# BG0249_R1M1E1_BW235_IMX378.net
KiCad netlist of a schematic drawn in Altium Designer
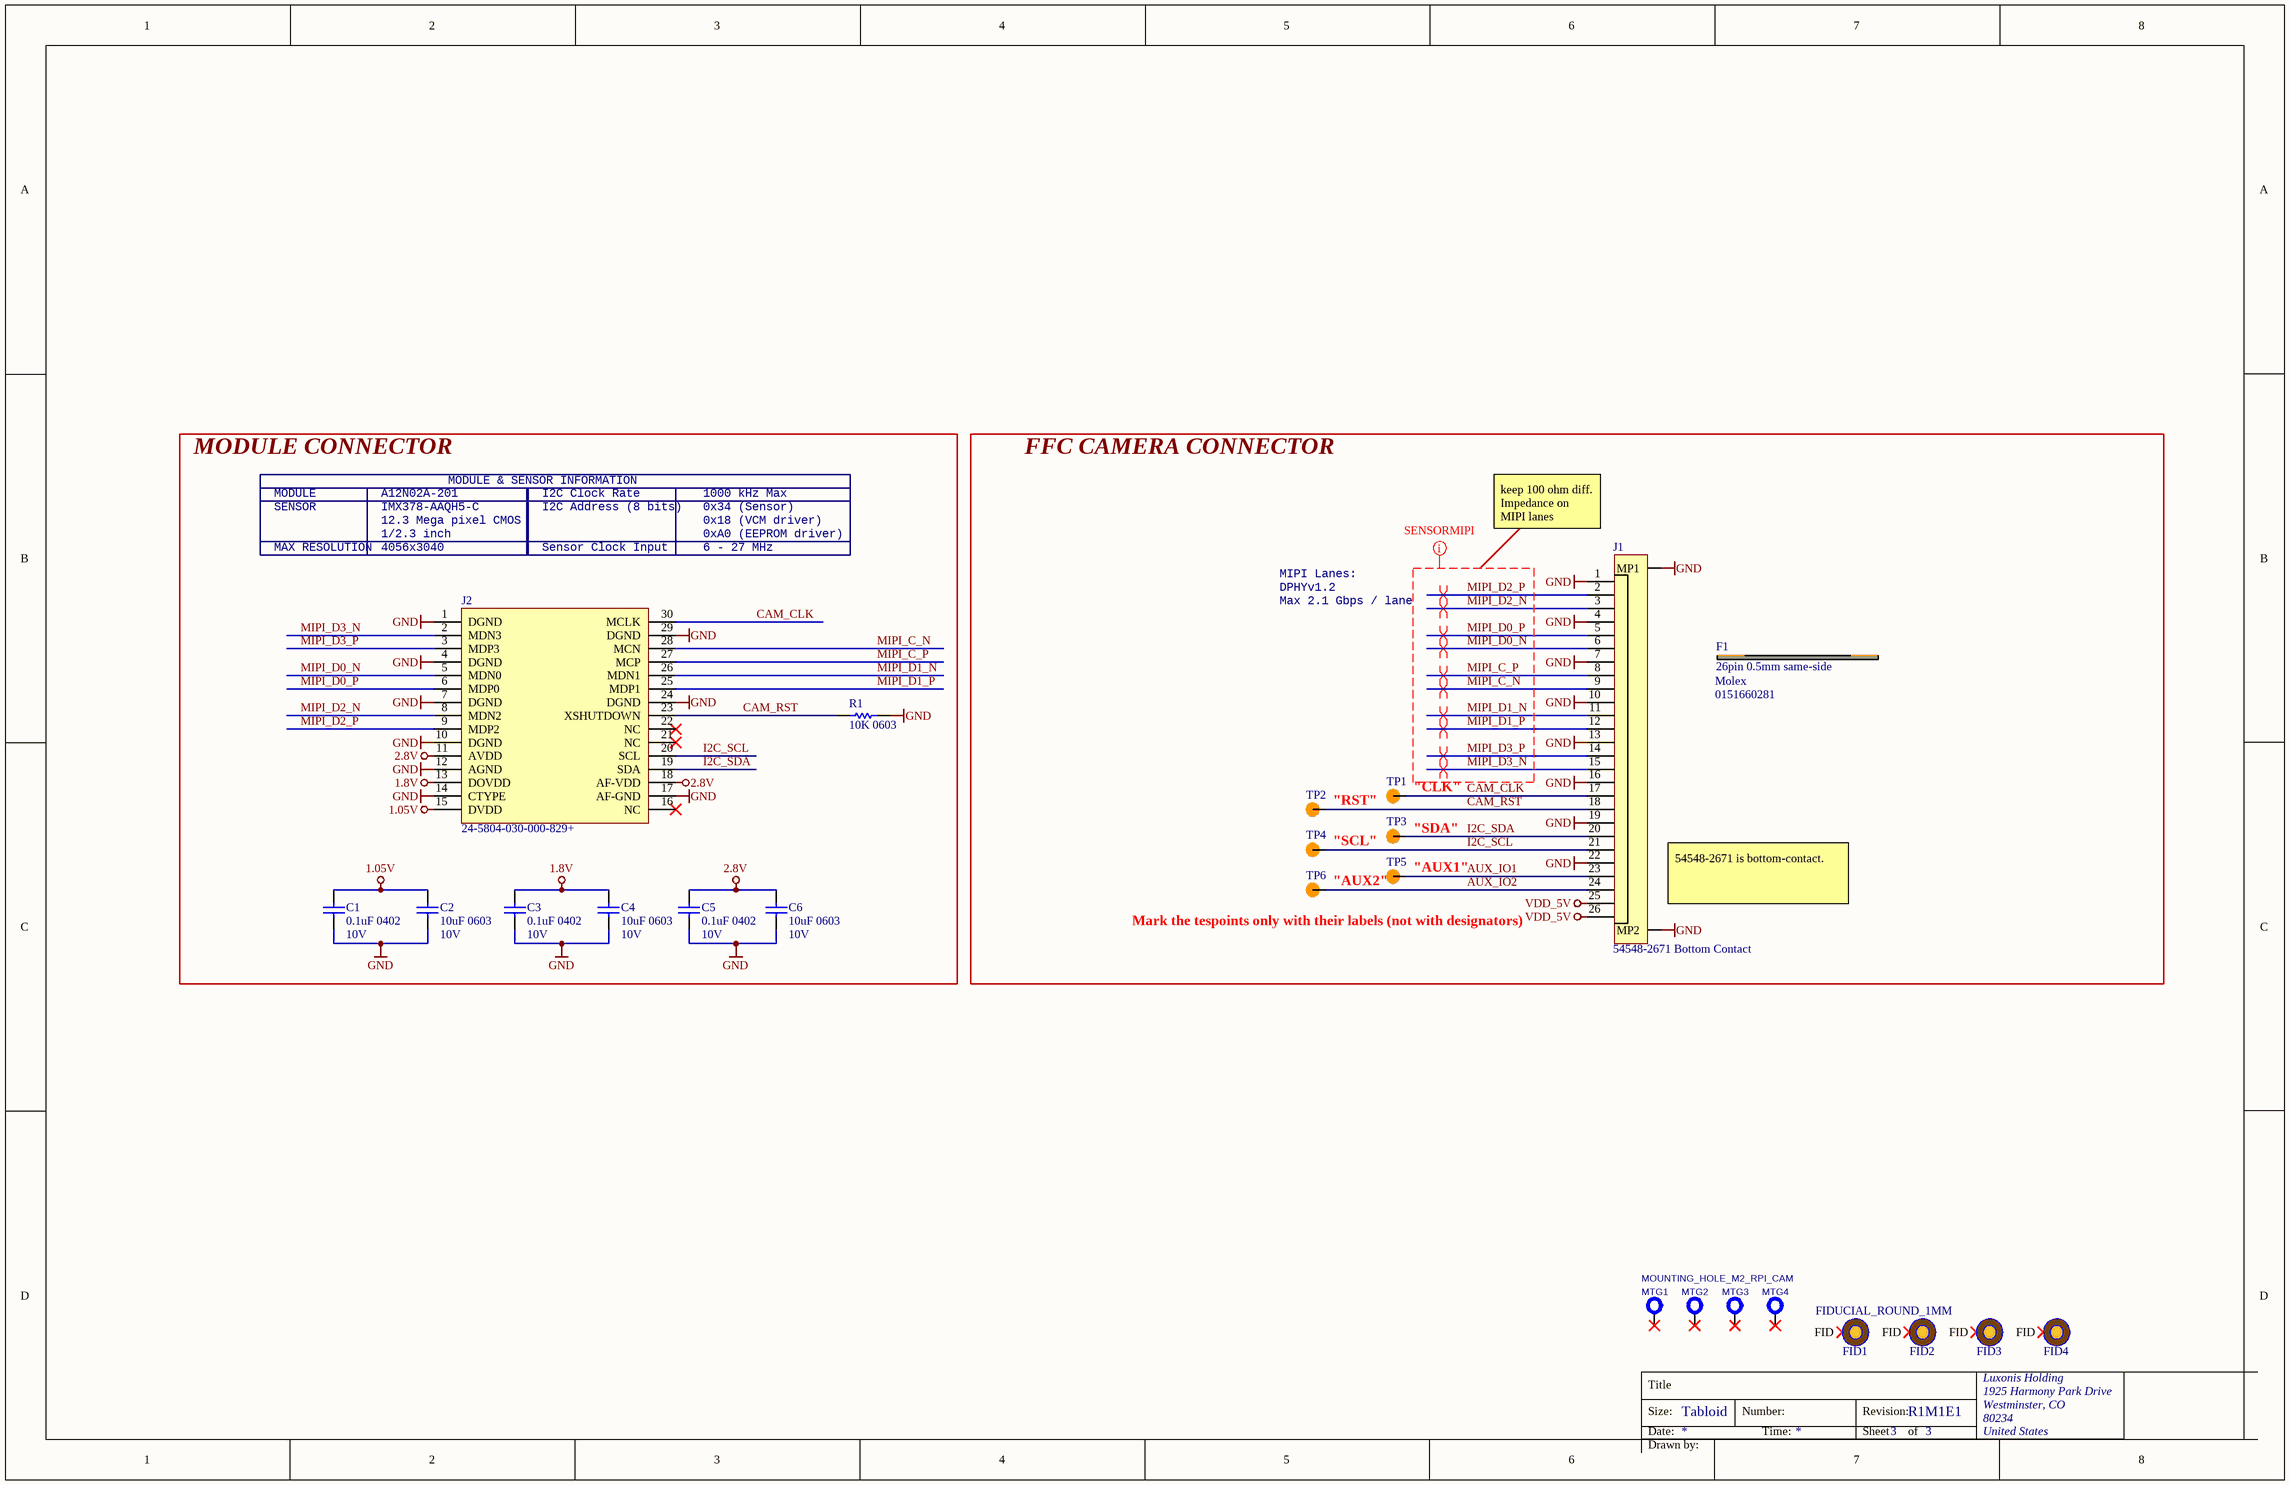
[diagram p0: BG0249_R1M1E1_BW235_IMX378.SchDoc]

(export (version "E")
  (design (tool "Eeschema 10.0.6"))
  (components
    (comp (ref "C1")
      (value "0.1uF 0402")
      (footprint "CAP_Altium_Vault_Generic:CAPC0402(1005)70_N")
      (description "CAP CER 0.1UF 10V X7R 0402 5%")
      (fields (field (name "TOLERANCE") "5%") (field (name "VOLTAGE RATING") "10V"))
      (libsource (lib "LuxonisMaster") (part "GRM155R71A104JA01D"))
    )
    (comp (ref "C2")
      (value "10uF 0603")
      (footprint "CAP_Altium_Vault_Generic:CAPC0603(1608)100_N")
      (description "CAP CER 10UF 10V X5R 0603 20%")
      (fields (field (name "TOLERANCE") "20%") (field (name "VOLTAGE RATING") "10V"))
      (libsource (lib "LuxonisMaster") (part "GRM188R61A106ME69D"))
    )
    (comp (ref "C3")
      (value "0.1uF 0402")
      (footprint "CAP_Altium_Vault_Generic:CAPC0402(1005)70_N")
      (description "CAP CER 0.1UF 10V X7R 0402 5%")
      (fields (field (name "TOLERANCE") "5%") (field (name "VOLTAGE RATING") "10V"))
      (libsource (lib "LuxonisMaster") (part "GRM155R71A104JA01D"))
    )
    (comp (ref "C4")
      (value "10uF 0603")
      (footprint "CAP_Altium_Vault_Generic:CAPC0603(1608)100_N")
      (description "CAP CER 10UF 10V X5R 0603 20%")
      (fields (field (name "TOLERANCE") "20%") (field (name "VOLTAGE RATING") "10V"))
      (libsource (lib "LuxonisMaster") (part "GRM188R61A106ME69D"))
    )
    (comp (ref "C5")
      (value "0.1uF 0402")
      (footprint "CAP_Altium_Vault_Generic:CAPC0402(1005)70_N")
      (description "CAP CER 0.1UF 10V X7R 0402 5%")
      (fields (field (name "TOLERANCE") "5%") (field (name "VOLTAGE RATING") "10V"))
      (libsource (lib "LuxonisMaster") (part "GRM155R71A104JA01D"))
    )
    (comp (ref "C6")
      (value "10uF 0603")
      (footprint "CAP_Altium_Vault_Generic:CAPC0603(1608)100_N")
      (description "CAP CER 10UF 10V X5R 0603 20%")
      (fields (field (name "TOLERANCE") "20%") (field (name "VOLTAGE RATING") "10V"))
      (libsource (lib "LuxonisMaster") (part "GRM188R61A106ME69D"))
    )
    (comp (ref "F1")
      (value "26pin 0.5mm same-side")
      (description "CABLE FFC 26POS 0.50MM 6\"")
      (fields
        (field (name "MANUFACTURER 1") "Molex")
        (field (name "MANUFACTURER PART NUMBER 1") "0151660281")
      )
      (libsource (lib "BG0249_R1M1E1") (part "0151660281"))
    )
    (comp (ref "FID1")
      (value "FIDUCIAL_ROUND_1MM")
      (footprint "LuxonisMaster:FIDUCIAL_ROUND_1MM")
      (description "Fiducial with various available footprints")
      (libsource (lib "LuxonisMaster") (part "FIDUCIAL"))
    )
    (comp (ref "FID2")
      (value "FIDUCIAL_ROUND_1MM")
      (footprint "LuxonisMaster:FIDUCIAL_ROUND_1MM")
      (description "Fiducial with various available footprints")
      (libsource (lib "LuxonisMaster") (part "FIDUCIAL"))
    )
    (comp (ref "FID3")
      (value "FIDUCIAL_ROUND_1MM")
      (footprint "LuxonisMaster:FIDUCIAL_ROUND_1MM")
      (description "Fiducial with various available footprints")
      (libsource (lib "LuxonisMaster") (part "FIDUCIAL"))
    )
    (comp (ref "FID4")
      (value "FIDUCIAL_ROUND_1MM")
      (footprint "LuxonisMaster:FIDUCIAL_ROUND_1MM")
      (description "Fiducial with various available footprints")
      (libsource (lib "LuxonisMaster") (part "FIDUCIAL"))
    )
    (comp (ref "J1")
      (value "54548-2671 Bottom Contact")
      (footprint "LuxonisMaster:54548-2671")
      (fields
        (field (name "MANUFACTURER_PART_NUMBER") "54548-2671")
        (field (name "MOUSER PART NUMBER") "538-54548-2671")
      )
      (libsource (lib "LuxonisMaster") (part "54548-2671"))
    )
    (comp (ref "J2")
      (value "24-5804-030-000-829+")
      (footprint "LuxonisMaster:A12N02A-201_MatedModule")
      (description "CONN Series 5804 board to board 0.4mm pitch 30 way connector")
      (libsource (lib "LuxonisMaster") (part "A12N02A-201_Connector"))
    )
    (comp (ref "MTG1")
      (value "MOUNTING_HOLE_M2_RPI_CAM")
      (footprint "LuxonisMaster:MOUNTING_HOLE_M2_RPI_CAM")
      (description "=CurrentFootprint")
      (libsource (lib "LuxonisMaster") (part "MP_Mounting-Holes"))
    )
    (comp (ref "MTG2")
      (value "MOUNTING_HOLE_M2_RPI_CAM")
      (footprint "LuxonisMaster:MOUNTING_HOLE_M2_RPI_CAM")
      (description "=CurrentFootprint")
      (libsource (lib "LuxonisMaster") (part "MP_Mounting-Holes"))
    )
    (comp (ref "MTG3")
      (value "MOUNTING_HOLE_M2_RPI_CAM")
      (footprint "LuxonisMaster:MOUNTING_HOLE_M2_RPI_CAM")
      (description "=CurrentFootprint")
      (libsource (lib "LuxonisMaster") (part "MP_Mounting-Holes"))
    )
    (comp (ref "MTG4")
      (value "MOUNTING_HOLE_M2_RPI_CAM")
      (footprint "LuxonisMaster:MOUNTING_HOLE_M2_RPI_CAM")
      (description "=CurrentFootprint")
      (libsource (lib "LuxonisMaster") (part "MP_Mounting-Holes"))
    )
    (comp (ref "R1")
      (value "10K 0603")
      (footprint "RES_Altium_Vault_Generic:RESC0603(1608)_N")
      (description "RES SMD 10K OHM 1% 1/10W 0603")
      (fields (field (name "TOLERANCE") "1%"))
      (libsource (lib "LuxonisMaster") (part "RC0603FR-0710KL"))
    )
    (comp (ref "TP1")
      (value "TP100_150_NS")
      (footprint "LuxonisMaster:TP100_150_NS")
      (libsource (lib "LuxonisMaster") (part "TEST_POINT"))
    )
    (comp (ref "TP2")
      (value "TP100_150_NS")
      (footprint "LuxonisMaster:TP100_150_NS")
      (libsource (lib "LuxonisMaster") (part "TEST_POINT"))
    )
    (comp (ref "TP3")
      (value "TP100_150_NS")
      (footprint "LuxonisMaster:TP100_150_NS")
      (libsource (lib "LuxonisMaster") (part "TEST_POINT"))
    )
    (comp (ref "TP4")
      (value "TP100_150_NS")
      (footprint "LuxonisMaster:TP100_150_NS")
      (libsource (lib "LuxonisMaster") (part "TEST_POINT"))
    )
    (comp (ref "TP5")
      (value "TP100_150_NS")
      (footprint "LuxonisMaster:TP100_150_NS")
      (libsource (lib "LuxonisMaster") (part "TEST_POINT"))
    )
    (comp (ref "TP6")
      (value "TP100_150_NS")
      (footprint "LuxonisMaster:TP100_150_NS")
      (libsource (lib "LuxonisMaster") (part "TEST_POINT"))
    )
  )
  (nets
    (net (code "1") (name "/AUX_IO1") (class "Default")
      (node (ref "J1") (pin "23") (pinfunction "23_23") (pintype "passive"))
      (node (ref "TP5") (pin "1") (pintype "passive"))
    )
    (net (code "2") (name "/AUX_IO2") (class "Default")
      (node (ref "J1") (pin "24") (pinfunction "24_24") (pintype "passive"))
      (node (ref "TP6") (pin "1") (pintype "passive"))
    )
    (net (code "3") (name "/CAM_CLK") (class "Default")
      (node (ref "J1") (pin "17") (pinfunction "17_17") (pintype "passive"))
      (node (ref "J2") (pin "30") (pinfunction "MCLK_30") (pintype "passive"))
      (node (ref "TP1") (pin "1") (pintype "passive"))
    )
    (net (code "4") (name "/CAM_RST") (class "Default")
      (node (ref "J1") (pin "18") (pinfunction "18_18") (pintype "passive"))
      (node (ref "J2") (pin "23") (pinfunction "XSHUTDOWN_23") (pintype "passive"))
      (node (ref "R1") (pin "1") (pinfunction "1_1") (pintype "passive"))
      (node (ref "TP2") (pin "1") (pintype "passive"))
    )
    (net (code "5") (name "/I2C_SCL") (class "Default")
      (node (ref "J1") (pin "21") (pinfunction "21_21") (pintype "passive"))
      (node (ref "J2") (pin "20") (pinfunction "SCL_20") (pintype "passive"))
      (node (ref "TP4") (pin "1") (pintype "passive"))
    )
    (net (code "6") (name "/I2C_SDA") (class "Default")
      (node (ref "J1") (pin "20") (pinfunction "20_20") (pintype "passive"))
      (node (ref "J2") (pin "19") (pinfunction "SDA_19") (pintype "passive"))
      (node (ref "TP3") (pin "1") (pintype "passive"))
    )
    (net (code "7") (name "/MIPI_C_N") (class "Default")
      (node (ref "J1") (pin "9") (pinfunction "9_9") (pintype "passive"))
      (node (ref "J2") (pin "28") (pinfunction "MCN_28") (pintype "passive"))
    )
    (net (code "8") (name "/MIPI_C_P") (class "Default")
      (node (ref "J1") (pin "8") (pinfunction "8_8") (pintype "passive"))
      (node (ref "J2") (pin "27") (pinfunction "MCP_27") (pintype "passive"))
    )
    (net (code "9") (name "/MIPI_D0_N") (class "Default")
      (node (ref "J1") (pin "6") (pinfunction "6_6") (pintype "passive"))
      (node (ref "J2") (pin "5") (pinfunction "MDN0_5") (pintype "passive"))
    )
    (net (code "10") (name "/MIPI_D0_P") (class "Default")
      (node (ref "J1") (pin "5") (pinfunction "5_5") (pintype "passive"))
      (node (ref "J2") (pin "6") (pinfunction "MDP0_6") (pintype "passive"))
    )
    (net (code "11") (name "/MIPI_D1_N") (class "Default")
      (node (ref "J1") (pin "11") (pinfunction "11_11") (pintype "passive"))
      (node (ref "J2") (pin "26") (pinfunction "MDN1_26") (pintype "passive"))
    )
    (net (code "12") (name "/MIPI_D1_P") (class "Default")
      (node (ref "J1") (pin "12") (pinfunction "12_12") (pintype "passive"))
      (node (ref "J2") (pin "25") (pinfunction "MDP1_25") (pintype "passive"))
    )
    (net (code "13") (name "/MIPI_D2_N") (class "Default")
      (node (ref "J1") (pin "3") (pinfunction "3_3") (pintype "passive"))
      (node (ref "J2") (pin "8") (pinfunction "MDN2_8") (pintype "passive"))
    )
    (net (code "14") (name "/MIPI_D2_P") (class "Default")
      (node (ref "J1") (pin "2") (pinfunction "2_2") (pintype "passive"))
      (node (ref "J2") (pin "9") (pinfunction "MDP2_9") (pintype "passive"))
    )
    (net (code "15") (name "/MIPI_D3_N") (class "Default")
      (node (ref "J1") (pin "15") (pinfunction "15_15") (pintype "passive"))
      (node (ref "J2") (pin "2") (pinfunction "MDN3_2") (pintype "passive"))
    )
    (net (code "16") (name "/MIPI_D3_P") (class "Default")
      (node (ref "J1") (pin "14") (pinfunction "14_14") (pintype "passive"))
      (node (ref "J2") (pin "3") (pinfunction "MDP3_3") (pintype "passive"))
    )
    (net (code "17") (name "1.05V") (class "Default")
      (node (ref "C1") (pin "2") (pinfunction "2_2") (pintype "passive"))
      (node (ref "C2") (pin "2") (pinfunction "2_2") (pintype "passive"))
      (node (ref "J2") (pin "15") (pinfunction "DVDD_15") (pintype "passive"))
    )
    (net (code "18") (name "1.8V") (class "Default")
      (node (ref "C3") (pin "2") (pinfunction "2_2") (pintype "passive"))
      (node (ref "C4") (pin "2") (pinfunction "2_2") (pintype "passive"))
      (node (ref "J2") (pin "13") (pinfunction "DOVDD_13") (pintype "passive"))
    )
    (net (code "19") (name "2.8V") (class "Default")
      (node (ref "C5") (pin "2") (pinfunction "2_2") (pintype "passive"))
      (node (ref "C6") (pin "2") (pinfunction "2_2") (pintype "passive"))
      (node (ref "J2") (pin "11") (pinfunction "AVDD_11") (pintype "passive"))
      (node (ref "J2") (pin "18") (pinfunction "AF-VDD_18") (pintype "passive"))
    )
    (net (code "20") (name "GND") (class "Default")
      (node (ref "C1") (pin "1") (pinfunction "1_1") (pintype "passive"))
      (node (ref "C2") (pin "1") (pinfunction "1_1") (pintype "passive"))
      (node (ref "C3") (pin "1") (pinfunction "1_1") (pintype "passive"))
      (node (ref "C4") (pin "1") (pinfunction "1_1") (pintype "passive"))
      (node (ref "C5") (pin "1") (pinfunction "1_1") (pintype "passive"))
      (node (ref "C6") (pin "1") (pinfunction "1_1") (pintype "passive"))
      (node (ref "J1") (pin "1") (pinfunction "1_1") (pintype "passive"))
      (node (ref "J1") (pin "10") (pinfunction "10_10") (pintype "passive"))
      (node (ref "J1") (pin "13") (pinfunction "13_13") (pintype "passive"))
      (node (ref "J1") (pin "16") (pinfunction "16_16") (pintype "passive"))
      (node (ref "J1") (pin "19") (pinfunction "19_19") (pintype "passive"))
      (node (ref "J1") (pin "22") (pinfunction "22_22") (pintype "passive"))
      (node (ref "J1") (pin "4") (pinfunction "4_4") (pintype "passive"))
      (node (ref "J1") (pin "7") (pinfunction "7_7") (pintype "passive"))
      (node (ref "J1") (pin "MP1") (pinfunction "MP1_MP1") (pintype "passive"))
      (node (ref "J1") (pin "MP2") (pinfunction "MP2_MP2") (pintype "passive"))
      (node (ref "J2") (pin "1") (pinfunction "DGND_1") (pintype "passive"))
      (node (ref "J2") (pin "10") (pinfunction "DGND_10") (pintype "passive"))
      (node (ref "J2") (pin "12") (pinfunction "AGND_12") (pintype "passive"))
      (node (ref "J2") (pin "14") (pinfunction "CTYPE_14") (pintype "passive"))
      (node (ref "J2") (pin "17") (pinfunction "AF-GND_17") (pintype "passive"))
      (node (ref "J2") (pin "24") (pinfunction "DGND_24") (pintype "passive"))
      (node (ref "J2") (pin "29") (pinfunction "DGND_29") (pintype "passive"))
      (node (ref "J2") (pin "4") (pinfunction "DGND_4") (pintype "passive"))
      (node (ref "J2") (pin "7") (pinfunction "DGND_7") (pintype "passive"))
      (node (ref "R1") (pin "2") (pinfunction "2_2") (pintype "passive"))
    )
    (net (code "21") (name "VDD_5V") (class "Default")
      (node (ref "J1") (pin "25") (pinfunction "25_25") (pintype "passive"))
      (node (ref "J1") (pin "26") (pinfunction "26_26") (pintype "passive"))
    )
    (net (code "22") (name "unconnected-(FID1-PadFID)") (class "Default")
      (node (ref "FID1") (pin "FID") (pinfunction "FID_FID") (pintype "input+no_connect"))
    )
    (net (code "23") (name "unconnected-(FID2-PadFID)") (class "Default")
      (node (ref "FID2") (pin "FID") (pinfunction "FID_FID") (pintype "input+no_connect"))
    )
    (net (code "24") (name "unconnected-(FID3-PadFID)") (class "Default")
      (node (ref "FID3") (pin "FID") (pinfunction "FID_FID") (pintype "input+no_connect"))
    )
    (net (code "25") (name "unconnected-(FID4-PadFID)") (class "Default")
      (node (ref "FID4") (pin "FID") (pinfunction "FID_FID") (pintype "input+no_connect"))
    )
    (net (code "26") (name "unconnected-(J2-NC-Pad16)") (class "Default")
      (node (ref "J2") (pin "16") (pinfunction "NC_16") (pintype "passive+no_connect"))
    )
    (net (code "27") (name "unconnected-(J2-NC-Pad21)") (class "Default")
      (node (ref "J2") (pin "21") (pinfunction "NC_21") (pintype "passive+no_connect"))
    )
    (net (code "28") (name "unconnected-(J2-NC-Pad22)") (class "Default")
      (node (ref "J2") (pin "22") (pinfunction "NC_22") (pintype "passive+no_connect"))
    )
    (net (code "29") (name "unconnected-(MTG1-Pad1)") (class "Default")
      (node (ref "MTG1") (pin "1") (pintype "passive+no_connect"))
    )
    (net (code "30") (name "unconnected-(MTG2-Pad1)") (class "Default")
      (node (ref "MTG2") (pin "1") (pintype "passive+no_connect"))
    )
    (net (code "31") (name "unconnected-(MTG3-Pad1)") (class "Default")
      (node (ref "MTG3") (pin "1") (pintype "passive+no_connect"))
    )
    (net (code "32") (name "unconnected-(MTG4-Pad1)") (class "Default")
      (node (ref "MTG4") (pin "1") (pintype "passive+no_connect"))
    )
  )
)
